# Prototype_Tx.net
KiCad netlist of a schematic drawn in EAGLE
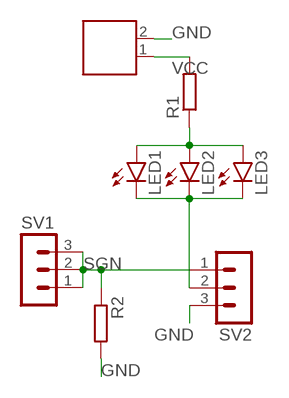
[diagram p0: schematic, sheet 1]

(export (version "E")
  (design (tool "Eeschema 10.0.6"))
  (components
    (comp (ref "12V")
      (value "691131710002")
      (footprint "eagle-import:691131710002")
      (libsource (lib "eagle-import") (part "691131710002"))
    )
    (comp (ref "LED1")
      (value "LEDCHIP-LED0805")
      (footprint "eagle-import:CHIP-LED0805")
      (libsource (lib "eagle-import") (part "LEDCHIP-LED0805"))
    )
    (comp (ref "LED2")
      (value "LEDCHIP-LED0805")
      (footprint "eagle-import:CHIP-LED0805")
      (libsource (lib "eagle-import") (part "LEDCHIP-LED0805"))
    )
    (comp (ref "LED3")
      (value "LEDCHIP-LED0805")
      (footprint "eagle-import:CHIP-LED0805")
      (libsource (lib "eagle-import") (part "LEDCHIP-LED0805"))
    )
    (comp (ref "R1")
      (value "R-EU_0207/10")
      (footprint "eagle-import:0207_10")
      (libsource (lib "eagle-import") (part "R-EU_0207/10"))
    )
    (comp (ref "R2")
      (value "R-EU_0204/7")
      (footprint "eagle-import:0204_7")
      (libsource (lib "eagle-import") (part "R-EU_0204/7"))
    )
    (comp (ref "SV1")
      (value "MA03-1")
      (footprint "eagle-import:MA03-1")
      (libsource (lib "eagle-import") (part "MA03-1"))
    )
    (comp (ref "SV2")
      (value "MA03-1")
      (footprint "eagle-import:MA03-1")
      (libsource (lib "eagle-import") (part "MA03-1"))
    )
  )
  (nets
    (net (code "1") (name "/GND") (class "Default")
      (node (ref "12V") (pin "2") (pinfunction "2_2") (pintype "passive"))
      (node (ref "R2") (pin "2") (pinfunction "2_2") (pintype "passive"))
      (node (ref "SV2") (pin "3") (pinfunction "3_3") (pintype "passive"))
    )
    (net (code "2") (name "/SGN") (class "Default")
      (node (ref "R2") (pin "1") (pinfunction "1_1") (pintype "passive"))
      (node (ref "SV1") (pin "1") (pinfunction "1_1") (pintype "passive"))
      (node (ref "SV1") (pin "2") (pinfunction "2_2") (pintype "passive"))
      (node (ref "SV1") (pin "3") (pinfunction "3_3") (pintype "passive"))
      (node (ref "SV2") (pin "1") (pinfunction "1_1") (pintype "passive"))
    )
    (net (code "3") (name "/VCC") (class "Default")
      (node (ref "12V") (pin "1") (pinfunction "1_1") (pintype "passive"))
      (node (ref "R1") (pin "2") (pinfunction "2_2") (pintype "passive"))
    )
    (net (code "4") (name "Net-(LED1-PadA)") (class "Default")
      (node (ref "LED1") (pin "A") (pinfunction "A_A") (pintype "passive"))
      (node (ref "LED2") (pin "A") (pinfunction "A_A") (pintype "passive"))
      (node (ref "LED3") (pin "A") (pinfunction "A_A") (pintype "passive"))
      (node (ref "R1") (pin "1") (pinfunction "1_1") (pintype "passive"))
    )
    (net (code "5") (name "Net-(LED1-PadC)") (class "Default")
      (node (ref "LED1") (pin "C") (pinfunction "C_C") (pintype "passive"))
      (node (ref "LED2") (pin "C") (pinfunction "C_C") (pintype "passive"))
      (node (ref "LED3") (pin "C") (pinfunction "C_C") (pintype "passive"))
      (node (ref "SV2") (pin "2") (pinfunction "2_2") (pintype "passive"))
    )
  )
)
